# Slave2.net
KiCad netlist of a schematic drawn in Altium Designer
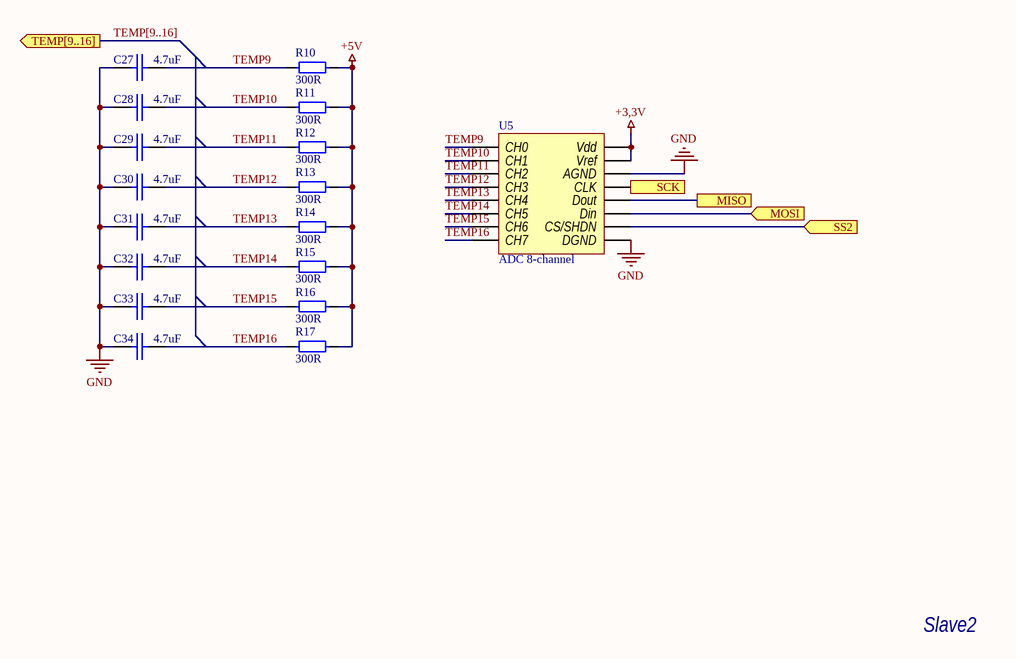
[diagram p0: Slave2.SchDoc]

(export (version "E")
  (design (tool "Eeschema 10.0.6"))
  (components
    (comp (ref "C27")
      (value "4.7uF")
      (footprint "0603 Capicator")
      (description "4.7uF X5R 25V 10% 0603")
      (fields
        (field (name "MANUFACTURER") "Murata Manufacturing")
        (field (name "PART NUMBER") "GRM188R61E475KE11D")
      )
      (libsource (lib "БУС") (part "Cap 4.7uF (0603)"))
    )
    (comp (ref "C28")
      (value "4.7uF")
      (footprint "0603 Capicator")
      (description "4.7uF X5R 25V 10% 0603")
      (fields
        (field (name "MANUFACTURER") "Murata Manufacturing")
        (field (name "PART NUMBER") "GRM188R61E475KE11D")
      )
      (libsource (lib "БУС") (part "Cap 4.7uF (0603)"))
    )
    (comp (ref "C29")
      (value "4.7uF")
      (footprint "0603 Capicator")
      (description "4.7uF X5R 25V 10% 0603")
      (fields
        (field (name "MANUFACTURER") "Murata Manufacturing")
        (field (name "PART NUMBER") "GRM188R61E475KE11D")
      )
      (libsource (lib "БУС") (part "Cap 4.7uF (0603)"))
    )
    (comp (ref "C30")
      (value "4.7uF")
      (footprint "0603 Capicator")
      (description "4.7uF X5R 25V 10% 0603")
      (fields
        (field (name "MANUFACTURER") "Murata Manufacturing")
        (field (name "PART NUMBER") "GRM188R61E475KE11D")
      )
      (libsource (lib "БУС") (part "Cap 4.7uF (0603)"))
    )
    (comp (ref "C31")
      (value "4.7uF")
      (footprint "0603 Capicator")
      (description "4.7uF X5R 25V 10% 0603")
      (fields
        (field (name "MANUFACTURER") "Murata Manufacturing")
        (field (name "PART NUMBER") "GRM188R61E475KE11D")
      )
      (libsource (lib "БУС") (part "Cap 4.7uF (0603)"))
    )
    (comp (ref "C32")
      (value "4.7uF")
      (footprint "0603 Capicator")
      (description "4.7uF X5R 25V 10% 0603")
      (fields
        (field (name "MANUFACTURER") "Murata Manufacturing")
        (field (name "PART NUMBER") "GRM188R61E475KE11D")
      )
      (libsource (lib "БУС") (part "Cap 4.7uF (0603)"))
    )
    (comp (ref "C33")
      (value "4.7uF")
      (footprint "0603 Capicator")
      (description "4.7uF X5R 25V 10% 0603")
      (fields
        (field (name "MANUFACTURER") "Murata Manufacturing")
        (field (name "PART NUMBER") "GRM188R61E475KE11D")
      )
      (libsource (lib "БУС") (part "Cap 4.7uF (0603)"))
    )
    (comp (ref "C34")
      (value "4.7uF")
      (footprint "0603 Capicator")
      (description "4.7uF X5R 25V 10% 0603")
      (fields
        (field (name "MANUFACTURER") "Murata Manufacturing")
        (field (name "PART NUMBER") "GRM188R61E475KE11D")
      )
      (libsource (lib "БУС") (part "Cap 4.7uF (0603)"))
    )
    (comp (ref "R10")
      (value "300R")
      (footprint "0603 Resistor")
      (description "0.1W 0603 300R, 1%")
      (fields (field (name "PART NUMBER") "RC0603FR-07360RL") (field (name "MANUFACTURER") "Taiwan"))
      (libsource (lib "БУС") (part "Res 300R (0603)"))
    )
    (comp (ref "R11")
      (value "300R")
      (footprint "0603 Resistor")
      (description "0.1W 0603 300R, 1%")
      (fields (field (name "PART NUMBER") "RC0603FR-07360RL") (field (name "MANUFACTURER") "Taiwan"))
      (libsource (lib "БУС") (part "Res 300R (0603)"))
    )
    (comp (ref "R12")
      (value "300R")
      (footprint "0603 Resistor")
      (description "0.1W 0603 300R, 1%")
      (fields (field (name "PART NUMBER") "RC0603FR-07360RL") (field (name "MANUFACTURER") "Taiwan"))
      (libsource (lib "БУС") (part "Res 300R (0603)"))
    )
    (comp (ref "R13")
      (value "300R")
      (footprint "0603 Resistor")
      (description "0.1W 0603 300R, 1%")
      (fields (field (name "PART NUMBER") "RC0603FR-07360RL") (field (name "MANUFACTURER") "Taiwan"))
      (libsource (lib "БУС") (part "Res 300R (0603)"))
    )
    (comp (ref "R14")
      (value "300R")
      (footprint "0603 Resistor")
      (description "0.1W 0603 300R, 1%")
      (fields (field (name "PART NUMBER") "RC0603FR-07360RL") (field (name "MANUFACTURER") "Taiwan"))
      (libsource (lib "БУС") (part "Res 300R (0603)"))
    )
    (comp (ref "R15")
      (value "300R")
      (footprint "0603 Resistor")
      (description "0.1W 0603 300R, 1%")
      (fields (field (name "PART NUMBER") "RC0603FR-07360RL") (field (name "MANUFACTURER") "Taiwan"))
      (libsource (lib "БУС") (part "Res 300R (0603)"))
    )
    (comp (ref "R16")
      (value "300R")
      (footprint "0603 Resistor")
      (description "0.1W 0603 300R, 1%")
      (fields (field (name "PART NUMBER") "RC0603FR-07360RL") (field (name "MANUFACTURER") "Taiwan"))
      (libsource (lib "БУС") (part "Res 300R (0603)"))
    )
    (comp (ref "R17")
      (value "300R")
      (footprint "0603 Resistor")
      (description "0.1W 0603 300R, 1%")
      (fields (field (name "PART NUMBER") "RC0603FR-07360RL") (field (name "MANUFACTURER") "Taiwan"))
      (libsource (lib "БУС") (part "Res 300R (0603)"))
    )
    (comp (ref "U5")
      (value "ADC 8-channel")
      (footprint "SOIC-16")
      (description "A/D converter with SPI serial interface")
      (fields (field (name "MANUFACTURER") "Microchip") (field (name "PART NUMBER") "MCP3008-I/SL"))
      (libsource (lib "БУС") (part "MCP3008-I/SL"))
    )
  )
  (nets
    (net (code "1") (name "+3,3V") (class "Default")
      (node (ref "U5") (pin "15") (pinfunction "Vref_15") (pintype "passive"))
      (node (ref "U5") (pin "16") (pinfunction "Vdd_16") (pintype "passive"))
    )
    (net (code "2") (name "+5V") (class "Default")
      (node (ref "R10") (pin "2") (pinfunction "2_2") (pintype "passive"))
      (node (ref "R11") (pin "2") (pinfunction "2_2") (pintype "passive"))
      (node (ref "R12") (pin "2") (pinfunction "2_2") (pintype "passive"))
      (node (ref "R13") (pin "2") (pinfunction "2_2") (pintype "passive"))
      (node (ref "R14") (pin "2") (pinfunction "2_2") (pintype "passive"))
      (node (ref "R15") (pin "2") (pinfunction "2_2") (pintype "passive"))
      (node (ref "R16") (pin "2") (pinfunction "2_2") (pintype "passive"))
      (node (ref "R17") (pin "2") (pinfunction "2_2") (pintype "passive"))
    )
    (net (code "3") (name "/MISO") (class "Default")
      (node (ref "U5") (pin "12") (pinfunction "Dout_12") (pintype "passive"))
    )
    (net (code "4") (name "/MOSI") (class "Default")
      (node (ref "U5") (pin "11") (pinfunction "Din_11") (pintype "passive"))
    )
    (net (code "5") (name "/SCK") (class "Default")
      (node (ref "U5") (pin "13") (pinfunction "CLK_13") (pintype "passive"))
    )
    (net (code "6") (name "/SS2") (class "Default")
      (node (ref "U5") (pin "10") (pinfunction "CS/SHDN_10") (pintype "passive"))
    )
    (net (code "7") (name "/TEMP9") (class "Default")
      (node (ref "C27") (pin "2") (pinfunction "2_2") (pintype "passive"))
      (node (ref "R10") (pin "1") (pinfunction "1_1") (pintype "passive"))
      (node (ref "U5") (pin "1") (pinfunction "CH0_1") (pintype "passive"))
    )
    (net (code "8") (name "/TEMP10") (class "Default")
      (node (ref "C28") (pin "2") (pinfunction "2_2") (pintype "passive"))
      (node (ref "R11") (pin "1") (pinfunction "1_1") (pintype "passive"))
      (node (ref "U5") (pin "2") (pinfunction "CH1_2") (pintype "passive"))
    )
    (net (code "9") (name "/TEMP11") (class "Default")
      (node (ref "C29") (pin "2") (pinfunction "2_2") (pintype "passive"))
      (node (ref "R12") (pin "1") (pinfunction "1_1") (pintype "passive"))
      (node (ref "U5") (pin "3") (pinfunction "CH2_3") (pintype "passive"))
    )
    (net (code "10") (name "/TEMP12") (class "Default")
      (node (ref "C30") (pin "2") (pinfunction "2_2") (pintype "passive"))
      (node (ref "R13") (pin "1") (pinfunction "1_1") (pintype "passive"))
      (node (ref "U5") (pin "4") (pinfunction "CH3_4") (pintype "passive"))
    )
    (net (code "11") (name "/TEMP13") (class "Default")
      (node (ref "C31") (pin "2") (pinfunction "2_2") (pintype "passive"))
      (node (ref "R14") (pin "1") (pinfunction "1_1") (pintype "passive"))
      (node (ref "U5") (pin "5") (pinfunction "CH4_5") (pintype "passive"))
    )
    (net (code "12") (name "/TEMP14") (class "Default")
      (node (ref "C32") (pin "2") (pinfunction "2_2") (pintype "passive"))
      (node (ref "R15") (pin "1") (pinfunction "1_1") (pintype "passive"))
      (node (ref "U5") (pin "6") (pinfunction "CH5_6") (pintype "passive"))
    )
    (net (code "13") (name "/TEMP15") (class "Default")
      (node (ref "C33") (pin "2") (pinfunction "2_2") (pintype "passive"))
      (node (ref "R16") (pin "1") (pinfunction "1_1") (pintype "passive"))
      (node (ref "U5") (pin "7") (pinfunction "CH6_7") (pintype "passive"))
    )
    (net (code "14") (name "/TEMP16") (class "Default")
      (node (ref "C34") (pin "2") (pinfunction "2_2") (pintype "passive"))
      (node (ref "R17") (pin "1") (pinfunction "1_1") (pintype "passive"))
      (node (ref "U5") (pin "8") (pinfunction "CH7_8") (pintype "passive"))
    )
    (net (code "16") (name "GND") (class "Default")
      (node (ref "C27") (pin "1") (pinfunction "1_1") (pintype "passive"))
      (node (ref "C28") (pin "1") (pinfunction "1_1") (pintype "passive"))
      (node (ref "C29") (pin "1") (pinfunction "1_1") (pintype "passive"))
      (node (ref "C30") (pin "1") (pinfunction "1_1") (pintype "passive"))
      (node (ref "C31") (pin "1") (pinfunction "1_1") (pintype "passive"))
      (node (ref "C32") (pin "1") (pinfunction "1_1") (pintype "passive"))
      (node (ref "C33") (pin "1") (pinfunction "1_1") (pintype "passive"))
      (node (ref "C34") (pin "1") (pinfunction "1_1") (pintype "passive"))
      (node (ref "U5") (pin "14") (pinfunction "AGND_14") (pintype "passive"))
      (node (ref "U5") (pin "9") (pinfunction "DGND_9") (pintype "passive"))
    )
  )
)
